# L506.net
KiCad netlist of a schematic drawn in Altium Designer
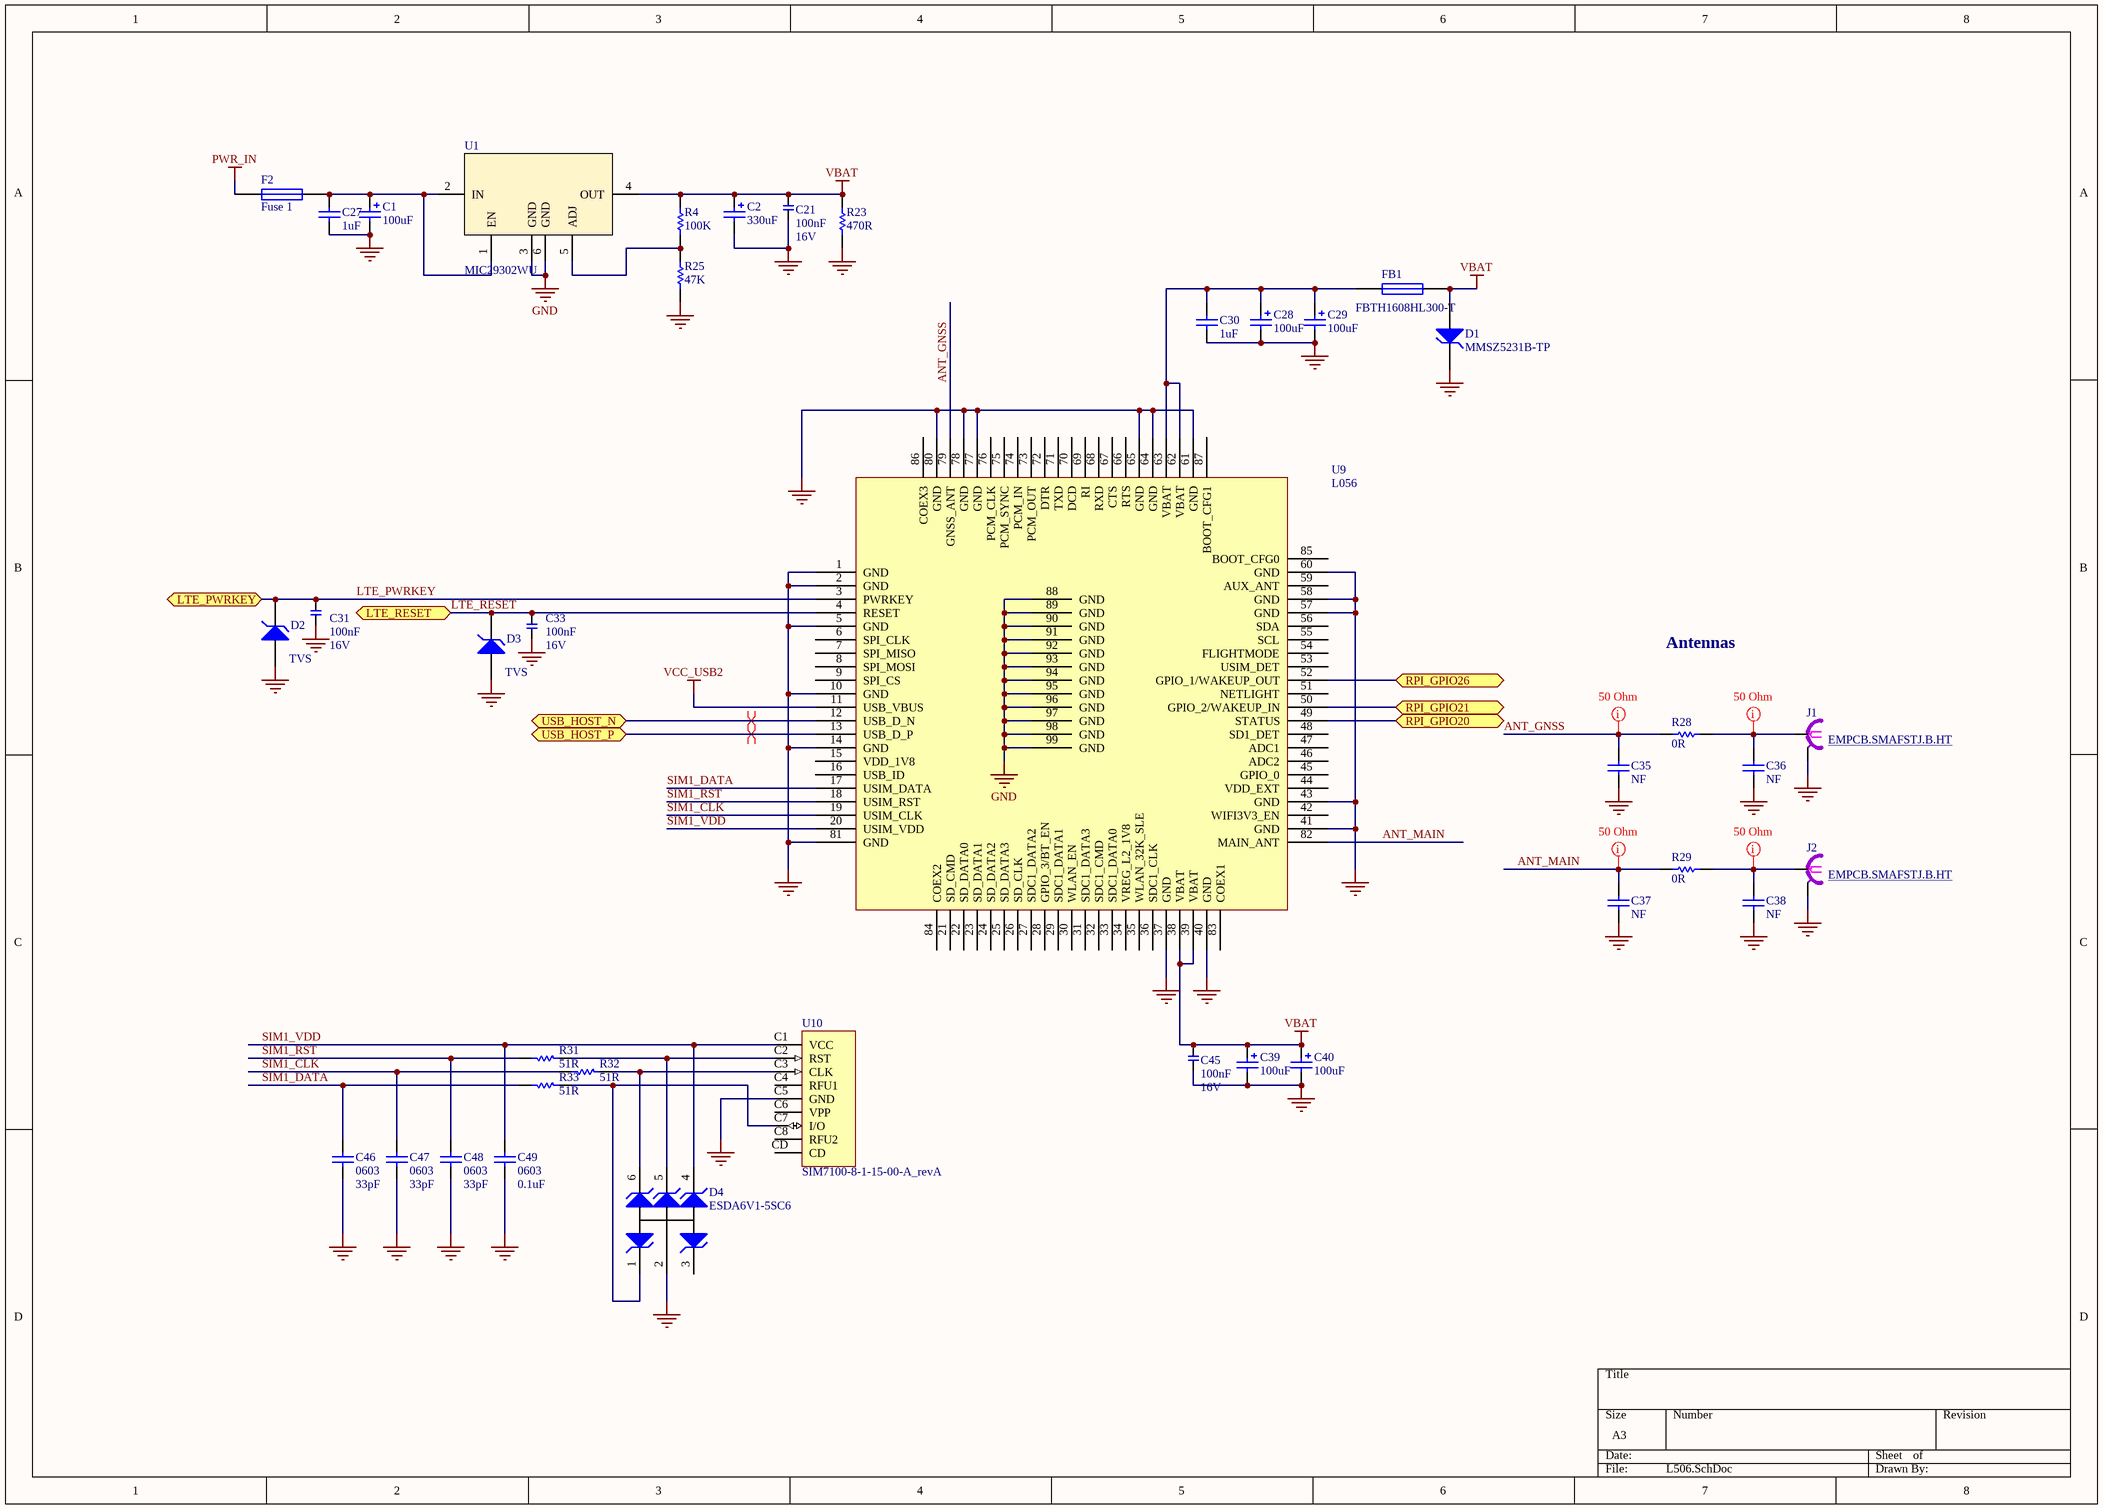
[diagram p0: L506.SchDoc]

(export (version "E")
  (design (tool "Eeschema 10.0.6"))
  (components
    (comp (ref "C1")
      (value "100uF")
      (footprint "2312 Tant")
      (description "Polarized Capacitor (Axial)")
      (fields (field (name "PUBLISHER") "Altium Limited"))
      (libsource (lib "Miscellaneous Devices") (part "Cap Pol2"))
    )
    (comp (ref "C2")
      (value "330uF")
      (footprint "2312 Tant")
      (description "Polarized Capacitor (Axial)")
      (fields (field (name "PUBLISHER") "Altium Limited"))
      (libsource (lib "Miscellaneous Devices") (part "Cap Pol2"))
    )
    (comp (ref "C21")
      (value "100nF")
      (footprint "T_CAPC0603X33N")
      (description "Capacitor Ceramic X7R 100nF 16V 10% 0603")
      (fields (field (name "TOLERANCE") "10%") (field (name "RATING") "16V"))
      (libsource (lib "Iris") (part "C-X7R-100nF-16V-10%-0603"))
    )
    (comp (ref "C27")
      (value "1uF")
      (footprint "CAPC1608X100N")
      (fields (field (name "MPN") "C0603C105K8PACTU"))
      (libsource (lib "Passive components") (part "CAP"))
    )
    (comp (ref "C28")
      (value "100uF")
      (footprint "2312 Tant")
      (description "Polarized Capacitor (Axial)")
      (fields (field (name "PUBLISHER") "Altium Limited"))
      (libsource (lib "Miscellaneous Devices") (part "Cap Pol2"))
    )
    (comp (ref "C29")
      (value "100uF")
      (footprint "2312 Tant")
      (description "Polarized Capacitor (Axial)")
      (fields (field (name "PUBLISHER") "Altium Limited"))
      (libsource (lib "Miscellaneous Devices") (part "Cap Pol2"))
    )
    (comp (ref "C30")
      (value "1uF")
      (footprint "CAPC1608X100N")
      (fields (field (name "MPN") "C0603C105K8PACTU"))
      (libsource (lib "Passive components") (part "CAP"))
    )
    (comp (ref "C31")
      (value "100nF")
      (footprint "T_CAPC0603X33N")
      (description "Capacitor Ceramic X7R 100nF 16V 10% 0603")
      (fields (field (name "TOLERANCE") "10%") (field (name "RATING") "16V"))
      (libsource (lib "Iris") (part "C-X7R-100nF-16V-10%-0603"))
    )
    (comp (ref "C33")
      (value "100nF")
      (footprint "T_CAPC0603X33N")
      (description "Capacitor Ceramic X7R 100nF 16V 10% 0603")
      (fields (field (name "TOLERANCE") "10%") (field (name "RATING") "16V"))
      (libsource (lib "Iris") (part "C-X7R-100nF-16V-10%-0603"))
    )
    (comp (ref "C35")
      (value "NF")
      (footprint "CAPC1608X100N")
      (description "CAP CER 10NF 50V 5% X7R 0805")
      (fields (field (name "MANUFACTURER PART NUMBER") "08055C103JAT2A"))
      (libsource (lib "altium-import") (part "root_1_CMP-16466678-5_"))
    )
    (comp (ref "C36")
      (value "NF")
      (footprint "CAPC1608X100N")
      (description "CAP CER 10NF 50V 5% X7R 0805")
      (fields (field (name "MANUFACTURER PART NUMBER") "08055C103JAT2A"))
      (libsource (lib "altium-import") (part "root_1_CAP-2_"))
    )
    (comp (ref "C37")
      (value "NF")
      (footprint "CAPC1608X100N")
      (description "CAP CER 10NF 50V 5% X7R 0805")
      (fields (field (name "MANUFACTURER PART NUMBER") "08055C103JAT2A"))
      (libsource (lib "altium-import") (part "root_1_CMP-16466678-5_"))
    )
    (comp (ref "C38")
      (value "NF")
      (footprint "CAPC1608X100N")
      (description "CAP CER 10NF 50V 5% X7R 0805")
      (fields (field (name "MANUFACTURER PART NUMBER") "08055C103JAT2A"))
      (libsource (lib "altium-import") (part "root_1_CAP-2_"))
    )
    (comp (ref "C39")
      (value "100uF")
      (footprint "2312 Tant")
      (description "Polarized Capacitor (Axial)")
      (fields (field (name "PUBLISHER") "Altium Limited"))
      (libsource (lib "Miscellaneous Devices") (part "Cap Pol2"))
    )
    (comp (ref "C40")
      (value "100uF")
      (footprint "2312 Tant")
      (description "Polarized Capacitor (Axial)")
      (fields (field (name "PUBLISHER") "Altium Limited"))
      (libsource (lib "Miscellaneous Devices") (part "Cap Pol2"))
    )
    (comp (ref "C45")
      (value "100nF")
      (footprint "T_CAPC0603X33N")
      (description "Capacitor Ceramic X7R 100nF 16V 10% 0603")
      (fields (field (name "TOLERANCE") "10%") (field (name "RATING") "16V"))
      (libsource (lib "Iris") (part "C-X7R-100nF-16V-10%-0603"))
    )
    (comp (ref "C46")
      (value "0603")
      (footprint "CAPC1608X100N")
      (description "CAP CER 33PF 50V C0G/NP0 0603")
      (fields (field (name "MANUFACTURER") "Kemet") (field (name "ALTIUM_VALUE") "33pF"))
      (libsource (lib "Passive components") (part "CAP"))
    )
    (comp (ref "C47")
      (value "0603")
      (footprint "CAPC1608X100N")
      (description "CAP CER 33PF 50V C0G/NP0 0603")
      (fields (field (name "MANUFACTURER") "Kemet") (field (name "ALTIUM_VALUE") "33pF"))
      (libsource (lib "Passive components") (part "CAP"))
    )
    (comp (ref "C48")
      (value "0603")
      (footprint "CAPC1608X100N")
      (description "CAP CER 33PF 50V C0G/NP0 0603")
      (fields (field (name "MANUFACTURER") "Kemet") (field (name "ALTIUM_VALUE") "33pF"))
      (libsource (lib "Passive components") (part "CAP"))
    )
    (comp (ref "C49")
      (value "0603")
      (footprint "CAPC1608X100N")
      (description "CAP CER 0.1UF 16V X7R 0603")
      (fields (field (name "MANUFACTURER") "Kemet") (field (name "ALTIUM_VALUE") "0.1uF"))
      (libsource (lib "Passive components") (part "CAP"))
    )
    (comp (ref "D1")
      (value "MMSZ5231B-TP")
      (footprint "SOD3715X145N")
      (description "Zener Diode")
      (fields (field (name "MANUFACTURER") "Micro Commercial Co") (field (name "PUBLISHER") "Altium Limited"))
      (libsource (lib "Miscellaneous Devices") (part "D Zener"))
    )
    (comp (ref "D2")
      (value "TVS")
      (footprint "SOD3715X145N")
      (description "Zener Diode")
      (fields (field (name "MANUFACTURER") "Micro Commercial Co") (field (name "PUBLISHER") "Altium Limited"))
      (libsource (lib "Miscellaneous Devices") (part "D Zener"))
    )
    (comp (ref "D3")
      (value "TVS")
      (footprint "SOD3715X145N")
      (description "Zener Diode")
      (fields (field (name "MANUFACTURER") "Micro Commercial Co") (field (name "PUBLISHER") "Altium Limited"))
      (libsource (lib "Miscellaneous Devices") (part "D Zener"))
    )
    (comp (ref "D4")
      (value "ESDA6V1-5SC6")
      (footprint "SOT95P280X100-6N")
      (description "ESDA Series 5 Channel 6.1 V 50 pF SMT Uni Directional Transil Array - SOT-23-6L")
      (libsource (lib "altium-import") (part "root_1_CMP-924f5b40f9684d88-1_"))
    )
    (comp (ref "F2")
      (value "Fuse 1")
      (footprint "SSQC_BEL")
      (description "Fuse")
      (fields (field (name "MPN") "SSQC 3"))
      (libsource (lib "Miscellaneous Devices") (part "Fuse 1"))
    )
    (comp (ref "FB1")
      (value "FBTH1608HL300-T")
      (footprint "IND-0603")
      (description "Fuse")
      (fields (field (name "MANUFACTURER PART NUMBER") "0ZRM0050FF1E"))
      (libsource (lib "Miscellaneous Devices") (part "Fuse 1"))
    )
    (comp (ref "J1")
      (value "EMPCB.SMAFSTJ.B.HT")
      (footprint "EMPCB.SMAFSTJ.B.HT")
      (description "RECPT ULTRA-MINI COAX SMD")
      (libsource (lib "altium-import") (part "root_0_SYM-U.FL_"))
    )
    (comp (ref "J2")
      (value "EMPCB.SMAFSTJ.B.HT")
      (footprint "EMPCB.SMAFSTJ.B.HT")
      (description "RECPT ULTRA-MINI COAX SMD")
      (libsource (lib "altium-import") (part "root_0_SYM-U.FL_"))
    )
    (comp (ref "R4")
      (value "100K")
      (footprint "RESC1608X50N")
      (description "Resistor")
      (fields (field (name "PUBLISHER") "Altium Limited"))
      (libsource (lib "Miscellaneous Devices") (part "Res1"))
    )
    (comp (ref "R23")
      (value "470R")
      (footprint "RESC1608X50N")
      (description "Resistor")
      (fields (field (name "PUBLISHER") "Altium Limited"))
      (libsource (lib "Miscellaneous Devices") (part "Res1"))
    )
    (comp (ref "R25")
      (value "47K")
      (footprint "RESC1608X50N")
      (description "Resistor")
      (fields (field (name "PUBLISHER") "Altium Limited"))
      (libsource (lib "Miscellaneous Devices") (part "Res1"))
    )
    (comp (ref "R28")
      (value "0R")
      (footprint "RESC1608X50N")
      (description "RES SMD 0.0 OHM JUMPER 1/3W 0805")
      (libsource (lib "altium-import") (part "root_0_RES-2_"))
    )
    (comp (ref "R29")
      (value "0R")
      (footprint "RESC1608X50N")
      (description "RES SMD 0.0 OHM JUMPER 1/3W 0805")
      (libsource (lib "altium-import") (part "root_0_RES-2_"))
    )
    (comp (ref "R31")
      (value "51R")
      (footprint "RESC1608X50N")
      (description "RES SMD 1K OHM 1% 1/10W 0603")
      (fields (field (name "MANUFACTURER") "Yageo"))
      (libsource (lib "Miscellaneous Devices") (part "Res1"))
    )
    (comp (ref "R32")
      (value "51R")
      (footprint "RESC1608X50N")
      (description "RES SMD 1K OHM 1% 1/10W 0603")
      (fields (field (name "MANUFACTURER") "Yageo"))
      (libsource (lib "Miscellaneous Devices") (part "Res1"))
    )
    (comp (ref "R33")
      (value "51R")
      (footprint "RESC1608X50N")
      (description "RES SMD 1K OHM 1% 1/10W 0603")
      (fields (field (name "MANUFACTURER") "Yageo"))
      (libsource (lib "Miscellaneous Devices") (part "Res1"))
    )
    (comp (ref "U1")
      (value "MIC29302WU")
      (footprint "MIC29302WU")
      (libsource (lib "Inlib") (part "MIC29302WU"))
    )
    (comp (ref "U9") (value "L056") (footprint "L506") (libsource (lib "Inlib") (part "L056")))
    (comp (ref "U10")
      (value "SIM7100-8-1-15-00-A_revA")
      (footprint "SIM7100-8-1-15-00-A_revA")
      (description "Micro SIM Card Connector - Push-Push Type, 8 Pin, SMT, 1.50mm Profile")
      (libsource (lib "Inlib") (part "SIM7100-8-1-15-00-A_revA"))
    )
  )
  (nets
    (net (code "1") (name "/ANT_GNSS") (class "Default")
      (node (ref "C35") (pin "2") (pinfunction "2_2") (pintype "passive"))
      (node (ref "R28") (pin "1") (pinfunction "1_1") (pintype "passive"))
      (node (ref "U9") (pin "79") (pinfunction "GNSS_ANT_79") (pintype "passive"))
    )
    (net (code "2") (name "/ANT_MAIN") (class "Default")
      (node (ref "C37") (pin "2") (pinfunction "2_2") (pintype "passive"))
      (node (ref "R29") (pin "1") (pinfunction "1_1") (pintype "passive"))
      (node (ref "U9") (pin "82") (pinfunction "MAIN_ANT_82") (pintype "passive"))
    )
    (net (code "3") (name "/LTE_PWRKEY") (class "Default")
      (node (ref "C31") (pin "2") (pinfunction "2_2") (pintype "passive"))
      (node (ref "D2") (pin "2") (pinfunction "K_2") (pintype "passive"))
      (node (ref "U9") (pin "3") (pinfunction "PWRKEY_3") (pintype "passive"))
    )
    (net (code "4") (name "/LTE_RESET") (class "Default")
      (node (ref "C33") (pin "2") (pinfunction "2_2") (pintype "passive"))
      (node (ref "D3") (pin "2") (pinfunction "K_2") (pintype "passive"))
      (node (ref "U9") (pin "4") (pinfunction "RESET_4") (pintype "passive"))
    )
    (net (code "5") (name "/RPI_GPIO20") (class "Default")
      (node (ref "U9") (pin "49") (pinfunction "STATUS_49") (pintype "passive"))
    )
    (net (code "6") (name "/RPI_GPIO21") (class "Default")
      (node (ref "U9") (pin "50") (pinfunction "GPIO_2/WAKEUP_IN_50") (pintype "passive"))
    )
    (net (code "7") (name "/RPI_GPIO26") (class "Default")
      (node (ref "U9") (pin "52") (pinfunction "GPIO_1/WAKEUP_OUT_52") (pintype "passive"))
    )
    (net (code "8") (name "/SIM1_CLK") (class "Default")
      (node (ref "C47") (pin "1") (pinfunction "1_1") (pintype "passive"))
      (node (ref "R32") (pin "1") (pinfunction "1_1") (pintype "passive"))
      (node (ref "U9") (pin "19") (pinfunction "USIM_CLK_19") (pintype "passive"))
    )
    (net (code "9") (name "/SIM1_DATA") (class "Default")
      (node (ref "C46") (pin "1") (pinfunction "1_1") (pintype "passive"))
      (node (ref "R33") (pin "1") (pinfunction "1_1") (pintype "passive"))
      (node (ref "U9") (pin "17") (pinfunction "USIM_DATA_17") (pintype "passive"))
    )
    (net (code "10") (name "/SIM1_RST") (class "Default")
      (node (ref "C48") (pin "1") (pinfunction "1_1") (pintype "passive"))
      (node (ref "R31") (pin "1") (pinfunction "1_1") (pintype "passive"))
      (node (ref "U9") (pin "18") (pinfunction "USIM_RST_18") (pintype "passive"))
    )
    (net (code "11") (name "/SIM1_VDD") (class "Default")
      (node (ref "C49") (pin "1") (pinfunction "1_1") (pintype "passive"))
      (node (ref "D4") (pin "4") (pinfunction "A_4") (pintype "passive"))
      (node (ref "U10") (pin "C1") (pinfunction "VCC_C1") (pintype "power_in"))
      (node (ref "U9") (pin "20") (pinfunction "USIM_VDD_20") (pintype "passive"))
    )
    (net (code "12") (name "/USB_HOST_N") (class "Default")
      (node (ref "U9") (pin "12") (pinfunction "USB_D_N_12") (pintype "passive"))
    )
    (net (code "13") (name "/USB_HOST_P") (class "Default")
      (node (ref "U9") (pin "13") (pinfunction "USB_D_P_13") (pintype "passive"))
    )
    (net (code "14") (name "GND") (class "Default")
      (node (ref "C1") (pin "2") (pinfunction "2_2") (pintype "passive"))
      (node (ref "C2") (pin "2") (pinfunction "2_2") (pintype "passive"))
      (node (ref "C21") (pin "1") (pinfunction "1_1") (pintype "passive"))
      (node (ref "C27") (pin "2") (pinfunction "2_2") (pintype "passive"))
      (node (ref "C28") (pin "2") (pinfunction "2_2") (pintype "passive"))
      (node (ref "C29") (pin "2") (pinfunction "2_2") (pintype "passive"))
      (node (ref "C30") (pin "2") (pinfunction "2_2") (pintype "passive"))
      (node (ref "C31") (pin "1") (pinfunction "1_1") (pintype "passive"))
      (node (ref "C33") (pin "1") (pinfunction "1_1") (pintype "passive"))
      (node (ref "C35") (pin "1") (pinfunction "1_1") (pintype "passive"))
      (node (ref "C36") (pin "1") (pinfunction "1_1") (pintype "passive"))
      (node (ref "C37") (pin "1") (pinfunction "1_1") (pintype "passive"))
      (node (ref "C38") (pin "1") (pinfunction "1_1") (pintype "passive"))
      (node (ref "C39") (pin "2") (pinfunction "2_2") (pintype "passive"))
      (node (ref "C40") (pin "2") (pinfunction "2_2") (pintype "passive"))
      (node (ref "C45") (pin "1") (pinfunction "1_1") (pintype "passive"))
      (node (ref "C46") (pin "2") (pinfunction "2_2") (pintype "passive"))
      (node (ref "C47") (pin "2") (pinfunction "2_2") (pintype "passive"))
      (node (ref "C48") (pin "2") (pinfunction "2_2") (pintype "passive"))
      (node (ref "C49") (pin "2") (pinfunction "2_2") (pintype "passive"))
      (node (ref "D1") (pin "2") (pinfunction "K_2") (pintype "passive"))
      (node (ref "D2") (pin "1") (pinfunction "A_1") (pintype "passive"))
      (node (ref "D3") (pin "1") (pinfunction "A_1") (pintype "passive"))
      (node (ref "D4") (pin "2") (pinfunction "K_2") (pintype "passive"))
      (node (ref "J1") (pin "2") (pinfunction "GND_2") (pintype "power_in"))
      (node (ref "J2") (pin "2") (pinfunction "GND_2") (pintype "power_in"))
      (node (ref "R23") (pin "2") (pinfunction "2_2") (pintype "passive"))
      (node (ref "R25") (pin "2") (pinfunction "2_2") (pintype "passive"))
      (node (ref "U1") (pin "3") (pinfunction "GND_3") (pintype "passive"))
      (node (ref "U1") (pin "6") (pinfunction "GND_6") (pintype "passive"))
      (node (ref "U10") (pin "C5") (pinfunction "GND_C5") (pintype "power_in"))
      (node (ref "U9") (pin "1") (pinfunction "GND_1") (pintype "passive"))
      (node (ref "U9") (pin "10") (pinfunction "GND_10") (pintype "passive"))
      (node (ref "U9") (pin "14") (pinfunction "GND_14") (pintype "passive"))
      (node (ref "U9") (pin "2") (pinfunction "GND_2") (pintype "passive"))
      (node (ref "U9") (pin "37") (pinfunction "GND_37") (pintype "passive"))
      (node (ref "U9") (pin "40") (pinfunction "GND_40") (pintype "passive"))
      (node (ref "U9") (pin "41") (pinfunction "GND_41") (pintype "passive"))
      (node (ref "U9") (pin "43") (pinfunction "GND_43") (pintype "passive"))
      (node (ref "U9") (pin "5") (pinfunction "GND_5") (pintype "passive"))
      (node (ref "U9") (pin "57") (pinfunction "GND_57") (pintype "passive"))
      (node (ref "U9") (pin "58") (pinfunction "GND_58") (pintype "passive"))
      (node (ref "U9") (pin "60") (pinfunction "GND_60") (pintype "passive"))
      (node (ref "U9") (pin "61") (pinfunction "GND_61") (pintype "passive"))
      (node (ref "U9") (pin "64") (pinfunction "GND_64") (pintype "passive"))
      (node (ref "U9") (pin "65") (pinfunction "GND_65") (pintype "passive"))
      (node (ref "U9") (pin "77") (pinfunction "GND_77") (pintype "passive"))
      (node (ref "U9") (pin "78") (pinfunction "GND_78") (pintype "passive"))
      (node (ref "U9") (pin "80") (pinfunction "GND_80") (pintype "passive"))
      (node (ref "U9") (pin "81") (pinfunction "GND_81") (pintype "passive"))
      (node (ref "U9") (pin "88") (pinfunction "GND_88") (pintype "passive"))
      (node (ref "U9") (pin "89") (pinfunction "GND_89") (pintype "passive"))
      (node (ref "U9") (pin "90") (pinfunction "GND_90") (pintype "passive"))
      (node (ref "U9") (pin "91") (pinfunction "GND_91") (pintype "passive"))
      (node (ref "U9") (pin "92") (pinfunction "GND_92") (pintype "passive"))
      (node (ref "U9") (pin "93") (pinfunction "GND_93") (pintype "passive"))
      (node (ref "U9") (pin "94") (pinfunction "GND_94") (pintype "passive"))
      (node (ref "U9") (pin "95") (pinfunction "GND_95") (pintype "passive"))
      (node (ref "U9") (pin "96") (pinfunction "GND_96") (pintype "passive"))
      (node (ref "U9") (pin "97") (pinfunction "GND_97") (pintype "passive"))
      (node (ref "U9") (pin "98") (pinfunction "GND_98") (pintype "passive"))
      (node (ref "U9") (pin "99") (pinfunction "GND_99") (pintype "passive"))
    )
    (net (code "15") (name "Net-(C28-Pad1)") (class "Default")
      (node (ref "C28") (pin "1") (pinfunction "1_1") (pintype "passive"))
      (node (ref "C29") (pin "1") (pinfunction "1_1") (pintype "passive"))
      (node (ref "C30") (pin "1") (pinfunction "1_1") (pintype "passive"))
      (node (ref "FB1") (pin "1") (pinfunction "1_1") (pintype "passive"))
      (node (ref "U9") (pin "62") (pinfunction "VBAT_62") (pintype "passive"))
      (node (ref "U9") (pin "63") (pinfunction "VBAT_63") (pintype "passive"))
    )
    (net (code "16") (name "Net-(J1-Signal)") (class "Default")
      (node (ref "C36") (pin "2") (pinfunction "2_2") (pintype "passive"))
      (node (ref "J1") (pin "1") (pinfunction "Signal_1") (pintype "passive"))
      (node (ref "R28") (pin "2") (pinfunction "2_2") (pintype "passive"))
    )
    (net (code "17") (name "Net-(J2-Signal)") (class "Default")
      (node (ref "C38") (pin "2") (pinfunction "2_2") (pintype "passive"))
      (node (ref "J2") (pin "1") (pinfunction "Signal_1") (pintype "passive"))
      (node (ref "R29") (pin "2") (pinfunction "2_2") (pintype "passive"))
    )
    (net (code "18") (name "Net-(U1-ADJ)") (class "Default")
      (node (ref "R25") (pin "1") (pinfunction "1_1") (pintype "passive"))
      (node (ref "R4") (pin "2") (pinfunction "2_2") (pintype "passive"))
      (node (ref "U1") (pin "5") (pinfunction "ADJ_5") (pintype "passive"))
    )
    (net (code "19") (name "Net-(U1-EN)") (class "Default")
      (node (ref "C1") (pin "1") (pinfunction "1_1") (pintype "passive"))
      (node (ref "C27") (pin "1") (pinfunction "1_1") (pintype "passive"))
      (node (ref "F2") (pin "2") (pinfunction "2_2") (pintype "passive"))
      (node (ref "U1") (pin "1") (pinfunction "EN_1") (pintype "passive"))
      (node (ref "U1") (pin "2") (pinfunction "IN_2") (pintype "passive"))
    )
    (net (code "20") (name "Net-(U10-CLK)") (class "Default")
      (node (ref "D4") (pin "6") (pinfunction "A_6") (pintype "passive"))
      (node (ref "R32") (pin "2") (pinfunction "2_2") (pintype "passive"))
      (node (ref "U10") (pin "C3") (pinfunction "CLK_C3") (pintype "input"))
    )
    (net (code "21") (name "Net-(U10-I{slash}O)") (class "Default")
      (node (ref "D4") (pin "1") (pinfunction "K_1") (pintype "passive"))
      (node (ref "R33") (pin "2") (pinfunction "2_2") (pintype "passive"))
      (node (ref "U10") (pin "C7") (pinfunction "I/O_C7") (pintype "bidirectional"))
    )
    (net (code "22") (name "Net-(U10-RST)") (class "Default")
      (node (ref "D4") (pin "5") (pinfunction "A_5") (pintype "passive"))
      (node (ref "R31") (pin "2") (pinfunction "2_2") (pintype "passive"))
      (node (ref "U10") (pin "C2") (pinfunction "RST_C2") (pintype "input"))
    )
    (net (code "23") (name "PWR_IN") (class "Default")
      (node (ref "F2") (pin "1") (pinfunction "1_1") (pintype "passive"))
    )
    (net (code "24") (name "VBAT") (class "Default")
      (node (ref "C2") (pin "1") (pinfunction "1_1") (pintype "passive"))
      (node (ref "C21") (pin "2") (pinfunction "2_2") (pintype "passive"))
      (node (ref "C39") (pin "1") (pinfunction "1_1") (pintype "passive"))
      (node (ref "C40") (pin "1") (pinfunction "1_1") (pintype "passive"))
      (node (ref "C45") (pin "2") (pinfunction "2_2") (pintype "passive"))
      (node (ref "D1") (pin "1") (pinfunction "A_1") (pintype "passive"))
      (node (ref "FB1") (pin "2") (pinfunction "2_2") (pintype "passive"))
      (node (ref "R23") (pin "1") (pinfunction "1_1") (pintype "passive"))
      (node (ref "R4") (pin "1") (pinfunction "1_1") (pintype "passive"))
      (node (ref "U1") (pin "4") (pinfunction "OUT_4") (pintype "passive"))
      (node (ref "U9") (pin "38") (pinfunction "VBAT_38") (pintype "passive"))
      (node (ref "U9") (pin "39") (pinfunction "VBAT_39") (pintype "passive"))
    )
    (net (code "25") (name "VCC_USB2") (class "Default")
      (node (ref "U9") (pin "11") (pinfunction "USB_VBUS_11") (pintype "passive"))
    )
    (net (code "26") (name "unconnected-(D4-K-Pad3)") (class "Default")
      (node (ref "D4") (pin "3") (pinfunction "K_3") (pintype "passive"))
    )
    (net (code "27") (name "unconnected-(U9-ADC1-Pad47)") (class "Default")
      (node (ref "U9") (pin "47") (pinfunction "ADC1_47") (pintype "passive"))
    )
    (net (code "28") (name "unconnected-(U9-ADC2-Pad46)") (class "Default")
      (node (ref "U9") (pin "46") (pinfunction "ADC2_46") (pintype "passive"))
    )
    (net (code "29") (name "unconnected-(U9-AUX_ANT-Pad59)") (class "Default")
      (node (ref "U9") (pin "59") (pinfunction "AUX_ANT_59") (pintype "passive"))
    )
    (net (code "30") (name "unconnected-(U9-BOOT_CFG0-Pad85)") (class "Default")
      (node (ref "U9") (pin "85") (pinfunction "BOOT_CFG0_85") (pintype "passive"))
    )
    (net (code "31") (name "unconnected-(U9-BOOT_CFG1-Pad87)") (class "Default")
      (node (ref "U9") (pin "87") (pinfunction "BOOT_CFG1_87") (pintype "passive"))
    )
    (net (code "32") (name "unconnected-(U9-COEX1-Pad83)") (class "Default")
      (node (ref "U9") (pin "83") (pinfunction "COEX1_83") (pintype "passive"))
    )
    (net (code "33") (name "unconnected-(U9-COEX2-Pad84)") (class "Default")
      (node (ref "U9") (pin "84") (pinfunction "COEX2_84") (pintype "passive"))
    )
    (net (code "34") (name "unconnected-(U9-COEX3-Pad86)") (class "Default")
      (node (ref "U9") (pin "86") (pinfunction "COEX3_86") (pintype "passive"))
    )
    (net (code "35") (name "unconnected-(U9-CTS-Pad67)") (class "Default")
      (node (ref "U9") (pin "67") (pinfunction "CTS_67") (pintype "passive"))
    )
    (net (code "36") (name "unconnected-(U9-DCD-Pad70)") (class "Default")
      (node (ref "U9") (pin "70") (pinfunction "DCD_70") (pintype "passive"))
    )
    (net (code "37") (name "unconnected-(U9-DTR-Pad72)") (class "Default")
      (node (ref "U9") (pin "72") (pinfunction "DTR_72") (pintype "passive"))
    )
    (net (code "38") (name "unconnected-(U9-FLIGHTMODE-Pad54)") (class "Default")
      (node (ref "U9") (pin "54") (pinfunction "FLIGHTMODE_54") (pintype "passive"))
    )
    (net (code "39") (name "unconnected-(U9-GPIO_0-Pad45)") (class "Default")
      (node (ref "U9") (pin "45") (pinfunction "GPIO_0_45") (pintype "passive"))
    )
    (net (code "40") (name "unconnected-(U9-GPIO_3{slash}BT_EN-Pad28)") (class "Default")
      (node (ref "U9") (pin "28") (pinfunction "GPIO_3/BT_EN_28") (pintype "passive"))
    )
    (net (code "41") (name "unconnected-(U9-NETLIGHT-Pad51)") (class "Default")
      (node (ref "U9") (pin "51") (pinfunction "NETLIGHT_51") (pintype "passive"))
    )
    (net (code "42") (name "unconnected-(U9-PCM_CLK-Pad76)") (class "Default")
      (node (ref "U9") (pin "76") (pinfunction "PCM_CLK_76") (pintype "passive"))
    )
    (net (code "43") (name "unconnected-(U9-PCM_IN-Pad74)") (class "Default")
      (node (ref "U9") (pin "74") (pinfunction "PCM_IN_74") (pintype "passive"))
    )
    (net (code "44") (name "unconnected-(U9-PCM_OUT-Pad73)") (class "Default")
      (node (ref "U9") (pin "73") (pinfunction "PCM_OUT_73") (pintype "passive"))
    )
    (net (code "45") (name "unconnected-(U9-PCM_SYNC-Pad75)") (class "Default")
      (node (ref "U9") (pin "75") (pinfunction "PCM_SYNC_75") (pintype "passive"))
    )
    (net (code "46") (name "unconnected-(U9-RI-Pad69)") (class "Default")
      (node (ref "U9") (pin "69") (pinfunction "RI_69") (pintype "passive"))
    )
    (net (code "47") (name "unconnected-(U9-RTS-Pad66)") (class "Default")
      (node (ref "U9") (pin "66") (pinfunction "RTS_66") (pintype "passive"))
    )
    (net (code "48") (name "unconnected-(U9-RXD-Pad68)") (class "Default")
      (node (ref "U9") (pin "68") (pinfunction "RXD_68") (pintype "passive"))
    )
    (net (code "49") (name "unconnected-(U9-SCL-Pad55)") (class "Default")
      (node (ref "U9") (pin "55") (pinfunction "SCL_55") (pintype "passive"))
    )
    (net (code "50") (name "unconnected-(U9-SD1_DET-Pad48)") (class "Default")
      (node (ref "U9") (pin "48") (pinfunction "SD1_DET_48") (pintype "passive"))
    )
    (net (code "51") (name "unconnected-(U9-SDA-Pad56)") (class "Default")
      (node (ref "U9") (pin "56") (pinfunction "SDA_56") (pintype "passive"))
    )
    (net (code "52") (name "unconnected-(U9-SDC1_CLK-Pad36)") (class "Default")
      (node (ref "U9") (pin "36") (pinfunction "SDC1_CLK_36") (pintype "passive"))
    )
    (net (code "53") (name "unconnected-(U9-SDC1_CMD-Pad32)") (class "Default")
      (node (ref "U9") (pin "32") (pinfunction "SDC1_CMD_32") (pintype "passive"))
    )
    (net (code "54") (name "unconnected-(U9-SDC1_DATA0-Pad33)") (class "Default")
      (node (ref "U9") (pin "33") (pinfunction "SDC1_DATA0_33") (pintype "passive"))
    )
    (net (code "55") (name "unconnected-(U9-SDC1_DATA1-Pad29)") (class "Default")
      (node (ref "U9") (pin "29") (pinfunction "SDC1_DATA1_29") (pintype "passive"))
    )
    (net (code "56") (name "unconnected-(U9-SDC1_DATA2-Pad27)") (class "Default")
      (node (ref "U9") (pin "27") (pinfunction "SDC1_DATA2_27") (pintype "passive"))
    )
    (net (code "57") (name "unconnected-(U9-SDC1_DATA3-Pad31)") (class "Default")
      (node (ref "U9") (pin "31") (pinfunction "SDC1_DATA3_31") (pintype "passive"))
    )
    (net (code "58") (name "unconnected-(U9-SD_CLK-Pad26)") (class "Default")
      (node (ref "U9") (pin "26") (pinfunction "SD_CLK_26") (pintype "passive"))
    )
    (net (code "59") (name "unconnected-(U9-SD_CMD-Pad21)") (class "Default")
      (node (ref "U9") (pin "21") (pinfunction "SD_CMD_21") (pintype "passive"))
    )
    (net (code "60") (name "unconnected-(U9-SD_DATA0-Pad22)") (class "Default")
      (node (ref "U9") (pin "22") (pinfunction "SD_DATA0_22") (pintype "passive"))
    )
    (net (code "61") (name "unconnected-(U9-SD_DATA1-Pad23)") (class "Default")
      (node (ref "U9") (pin "23") (pinfunction "SD_DATA1_23") (pintype "passive"))
    )
    (net (code "62") (name "unconnected-(U9-SD_DATA2-Pad24)") (class "Default")
      (node (ref "U9") (pin "24") (pinfunction "SD_DATA2_24") (pintype "passive"))
    )
    (net (code "63") (name "unconnected-(U9-SD_DATA3-Pad25)") (class "Default")
      (node (ref "U9") (pin "25") (pinfunction "SD_DATA3_25") (pintype "passive"))
    )
    (net (code "64") (name "unconnected-(U9-SPI_CLK-Pad6)") (class "Default")
      (node (ref "U9") (pin "6") (pinfunction "SPI_CLK_6") (pintype "passive"))
    )
    (net (code "65") (name "unconnected-(U9-SPI_CS-Pad9)") (class "Default")
      (node (ref "U9") (pin "9") (pinfunction "SPI_CS_9") (pintype "passive"))
    )
    (net (code "66") (name "unconnected-(U9-SPI_MISO-Pad7)") (class "Default")
      (node (ref "U9") (pin "7") (pinfunction "SPI_MISO_7") (pintype "passive"))
    )
    (net (code "67") (name "unconnected-(U9-SPI_MOSI-Pad8)") (class "Default")
      (node (ref "U9") (pin "8") (pinfunction "SPI_MOSI_8") (pintype "passive"))
    )
    (net (code "68") (name "unconnected-(U9-TXD-Pad71)") (class "Default")
      (node (ref "U9") (pin "71") (pinfunction "TXD_71") (pintype "passive"))
    )
    (net (code "69") (name "unconnected-(U9-USB_ID-Pad16)") (class "Default")
      (node (ref "U9") (pin "16") (pinfunction "USB_ID_16") (pintype "passive"))
    )
    (net (code "70") (name "unconnected-(U9-USIM_DET-Pad53)") (class "Default")
      (node (ref "U9") (pin "53") (pinfunction "USIM_DET_53") (pintype "passive"))
    )
    (net (code "71") (name "unconnected-(U9-VDD_1V8-Pad15)") (class "Default")
      (node (ref "U9") (pin "15") (pinfunction "VDD_1V8_15") (pintype "passive"))
    )
    (net (code "72") (name "unconnected-(U9-VDD_EXT-Pad44)") (class "Default")
      (node (ref "U9") (pin "44") (pinfunction "VDD_EXT_44") (pintype "passive"))
    )
    (net (code "73") (name "unconnected-(U9-VREG_L2_1V8-Pad34)") (class "Default")
      (node (ref "U9") (pin "34") (pinfunction "VREG_L2_1V8_34") (pintype "passive"))
    )
    (net (code "74") (name "unconnected-(U9-WIFI3V3_EN-Pad42)") (class "Default")
      (node (ref "U9") (pin "42") (pinfunction "WIFI3V3_EN_42") (pintype "passive"))
    )
    (net (code "75") (name "unconnected-(U9-WLAN_32K_SLE-Pad35)") (class "Default")
      (node (ref "U9") (pin "35") (pinfunction "WLAN_32K_SLE_35") (pintype "passive"))
    )
    (net (code "76") (name "unconnected-(U9-WLAN_EN-Pad30)") (class "Default")
      (node (ref "U9") (pin "30") (pinfunction "WLAN_EN_30") (pintype "passive"))
    )
    (net (code "77") (name "unconnected-(U10-PadCD)") (class "Default")
      (node (ref "U10") (pin "CD") (pinfunction "CD_CD") (pintype "passive"))
    )
    (net (code "78") (name "unconnected-(U10-RFU1-PadC4)") (class "Default")
      (node (ref "U10") (pin "C4") (pinfunction "RFU1_C4") (pintype "passive"))
    )
    (net (code "79") (name "unconnected-(U10-RFU2-PadC8)") (class "Default")
      (node (ref "U10") (pin "C8") (pinfunction "RFU2_C8") (pintype "passive"))
    )
    (net (code "80") (name "unconnected-(U10-VPP-PadC6)") (class "Default")
      (node (ref "U10") (pin "C6") (pinfunction "VPP_C6") (pintype "power_in"))
    )
  )
)
